# Other_Componentt.net
KiCad netlist of a schematic drawn in Altium Designer
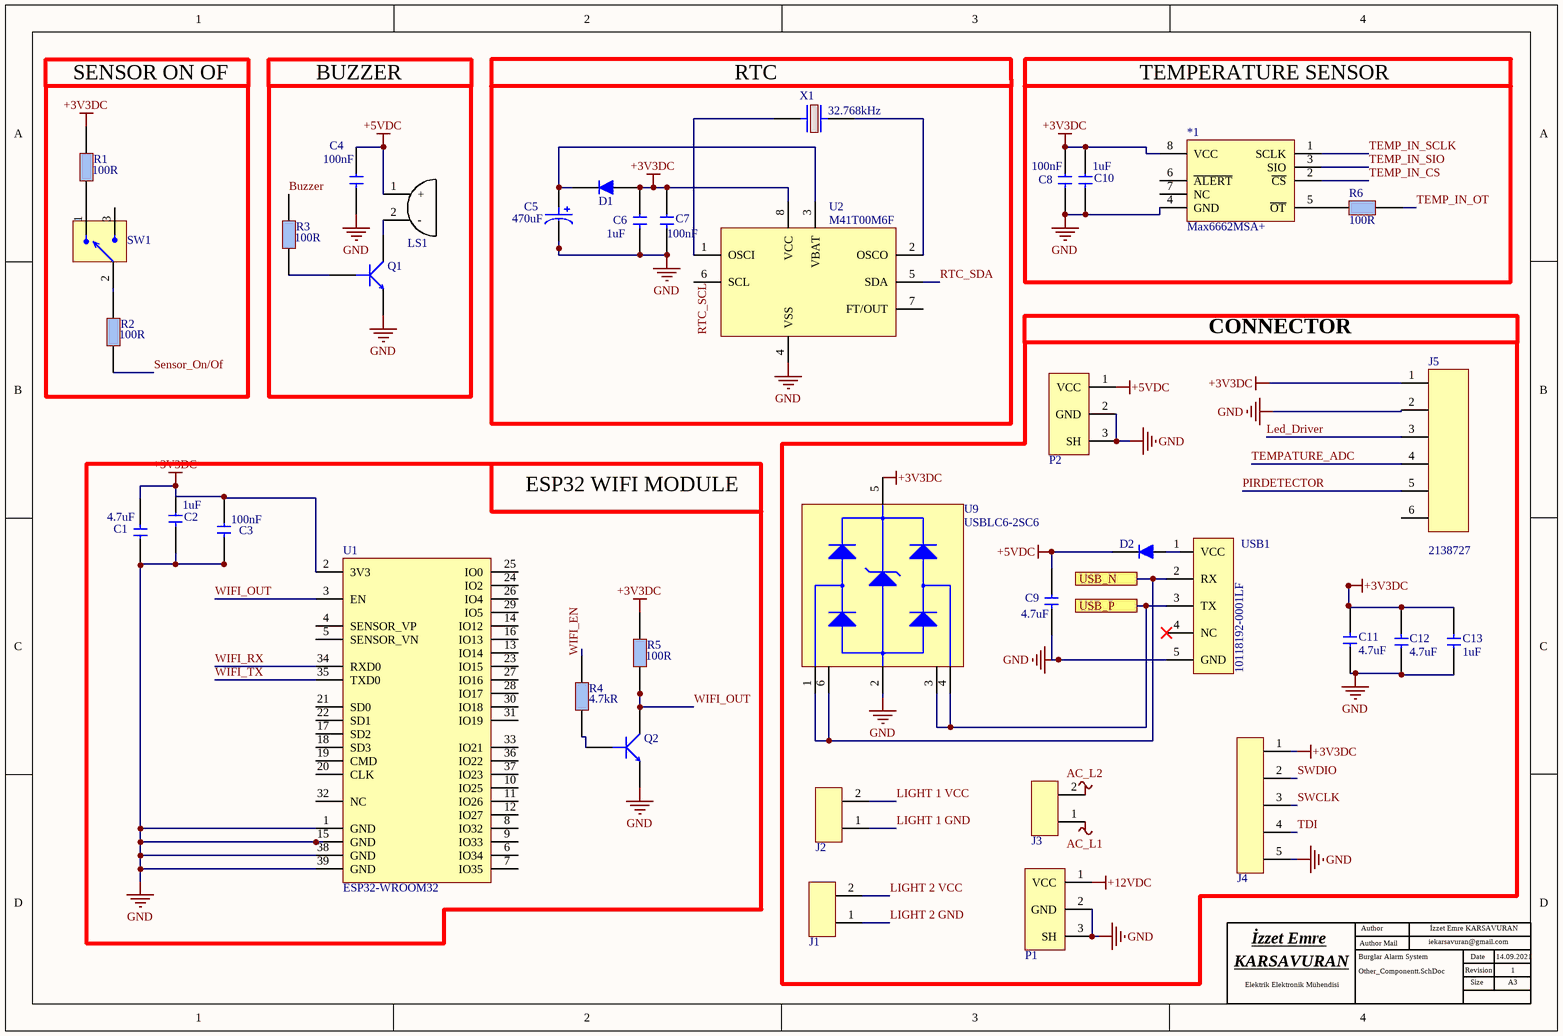
[diagram p0: Other_Componentt.SchDoc]

(export (version "E")
  (design (tool "Eeschema 10.0.6"))
  (components
    (comp (ref "*1")
      (value "Max6662MSA+")
      (footprint "SOIC8")
      (description "Temp Sensor Digital Serial (3-Wire, SPI) 8-Pin SOIC N Tube")
      (fields
        (field (name "MANUFACTURER") "Maxim")
        (field (name "MANUFACTURER PART NUMBER") "MAX6662MSA+")
        (field (name "DESIGNED BY") "İzzet Emre KARSAVURAN")
      )
      (libsource (lib "burglar_alarm_system_Library") (part "Max6662MSA+"))
    )
    (comp (ref "C1")
      (value "CL21A475KAQNNNE")
      (footprint "CAP_0805")
      (fields
        (field (name "MANUFACTURER") "Samsung")
        (field (name "TOLERANCE") "10%")
        (field (name "CAPACITANCE") "4.7uF")
        (field (name "DESIGNED BY") "İzzet Emre KARSAVURAN")
      )
      (libsource (lib "burglar_alarm_system_Library") (part "CAP CER 4.7uF"))
    )
    (comp (ref "C2")
      (value "CL21B105KBFNNNE")
      (footprint "CAP_0805")
      (fields
        (field (name "MANUFACTURER") "Samsung")
        (field (name "TOLERANCE") "10%")
        (field (name "VOLTAGE") "50V")
        (field (name "CAPACITANCE") "1uF")
        (field (name "DESIGNED BY") "İzzet Emre KARSAVURAN")
      )
      (libsource (lib "burglar_alarm_system_Library") (part "CAP CER 1uF"))
    )
    (comp (ref "C3")
      (value "CL21B104KBCNNNC")
      (footprint "CAP_0805")
      (fields
        (field (name "MANUFACTURER") "Samsung")
        (field (name "TOLERANCE") "10%")
        (field (name "VOLTAGE") "50V")
        (field (name "CAPACITANCE") "100nF")
        (field (name "DESIGNED BY") "İzzet Emre KARSAVURAN")
      )
      (libsource (lib "burglar_alarm_system_Library") (part "CAP CER 100nF-0803"))
    )
    (comp (ref "C4")
      (value "CL21B104KBCNNNC")
      (footprint "CAP_0805")
      (fields
        (field (name "MANUFACTURER") "Samsung")
        (field (name "TOLERANCE") "10%")
        (field (name "VOLTAGE") "50V")
        (field (name "CAPACITANCE") "100nF")
        (field (name "DESIGNED BY") "İzzet Emre KARSAVURAN")
      )
      (libsource (lib "burglar_alarm_system_Library") (part "CAP CER 100nF-0803"))
    )
    (comp (ref "C5")
      (value "ESH477M050AH4AA")
      (footprint "CAP_RADIAL_D10_P5")
      (description "Cap, 470UF, 50V, Alu Elec, Radial")
      (fields
        (field (name "MANUFACTURER") "KEMET")
        (field (name "TOLERANCE") "20%")
        (field (name "CAPACITANCE") "470uF")
        (field (name "DESIGNED BY") "İzzet Emre KARSAVURAN")
      )
      (libsource (lib "burglar_alarm_system_Library") (part "CAP ALU ELEC 470uF 50V"))
    )
    (comp (ref "C6")
      (value "CL21B105KBFNNNE")
      (footprint "CAP_0805")
      (fields
        (field (name "MANUFACTURER") "Samsung")
        (field (name "TOLERANCE") "10%")
        (field (name "VOLTAGE") "50V")
        (field (name "CAPACITANCE") "1uF")
        (field (name "DESIGNED BY") "İzzet Emre KARSAVURAN")
      )
      (libsource (lib "burglar_alarm_system_Library") (part "CAP CER 1uF"))
    )
    (comp (ref "C7")
      (value "CL21B104KBCNNNC")
      (footprint "CAP_0805")
      (fields
        (field (name "MANUFACTURER") "Samsung")
        (field (name "TOLERANCE") "10%")
        (field (name "VOLTAGE") "50V")
        (field (name "CAPACITANCE") "100nF")
        (field (name "DESIGNED BY") "İzzet Emre KARSAVURAN")
      )
      (libsource (lib "burglar_alarm_system_Library") (part "CAP CER 100nF-0803"))
    )
    (comp (ref "C8")
      (value "CL21B104KBCNNNC")
      (footprint "CAP_0805")
      (fields
        (field (name "MANUFACTURER") "Samsung")
        (field (name "TOLERANCE") "10%")
        (field (name "VOLTAGE") "50V")
        (field (name "CAPACITANCE") "100nF")
        (field (name "DESIGNED BY") "İzzet Emre KARSAVURAN")
      )
      (libsource (lib "burglar_alarm_system_Library") (part "CAP CER 100nF-0803"))
    )
    (comp (ref "C9")
      (value "CL21A475KAQNNNE")
      (footprint "CAP_0805")
      (fields
        (field (name "MANUFACTURER") "Samsung")
        (field (name "TOLERANCE") "10%")
        (field (name "CAPACITANCE") "4.7uF")
        (field (name "DESIGNED BY") "İzzet Emre KARSAVURAN")
      )
      (libsource (lib "burglar_alarm_system_Library") (part "CAP CER 4.7uF"))
    )
    (comp (ref "C10")
      (value "CL21B105KBFNNNE")
      (footprint "CAP_0805")
      (fields
        (field (name "MANUFACTURER") "Samsung")
        (field (name "TOLERANCE") "10%")
        (field (name "VOLTAGE") "50V")
        (field (name "CAPACITANCE") "1uF")
        (field (name "DESIGNED BY") "İzzet Emre KARSAVURAN")
      )
      (libsource (lib "burglar_alarm_system_Library") (part "CAP CER 1uF"))
    )
    (comp (ref "C11")
      (value "CL21A475KAQNNNE")
      (footprint "CAP_0805")
      (fields
        (field (name "MANUFACTURER") "Samsung")
        (field (name "TOLERANCE") "10%")
        (field (name "CAPACITANCE") "4.7uF")
        (field (name "DESIGNED BY") "İzzet Emre KARSAVURAN")
      )
      (libsource (lib "burglar_alarm_system_Library") (part "CAP CER 4.7uF"))
    )
    (comp (ref "C12")
      (value "CL21A475KAQNNNE")
      (footprint "CAP_0805")
      (fields
        (field (name "MANUFACTURER") "Samsung")
        (field (name "TOLERANCE") "10%")
        (field (name "CAPACITANCE") "4.7uF")
        (field (name "DESIGNED BY") "İzzet Emre KARSAVURAN")
      )
      (libsource (lib "burglar_alarm_system_Library") (part "CAP CER 4.7uF"))
    )
    (comp (ref "C13")
      (value "CL21B105KBFNNNE")
      (footprint "CAP_0805")
      (fields
        (field (name "MANUFACTURER") "Samsung")
        (field (name "TOLERANCE") "10%")
        (field (name "VOLTAGE") "50V")
        (field (name "CAPACITANCE") "1uF")
        (field (name "DESIGNED BY") "İzzet Emre KARSAVURAN")
      )
      (libsource (lib "burglar_alarm_system_Library") (part "CAP CER 1uF"))
    )
    (comp (ref "D1")
      (value "1N4148WS")
      (footprint "SOT23-F")
      (description "ON SEMICONDUCTOR - 1N4148WS - Small Signal Diode, Single, 75 V, 150 mA, 1 V, 4 ns")
      (fields
        (field (name "MANUFACTURER") "ON Semiconductor / Fairchild")
        (field (name "DESIGNED BY") "İzzet Emre KARSAVURAN")
      )
      (libsource (lib "burglar_alarm_system_Library") (part "1N4148WS"))
    )
    (comp (ref "D2")
      (value "1N4148WS")
      (footprint "SOT23-F")
      (description "ON SEMICONDUCTOR - 1N4148WS - Small Signal Diode, Single, 75 V, 150 mA, 1 V, 4 ns")
      (fields
        (field (name "MANUFACTURER") "ON Semiconductor / Fairchild")
        (field (name "DESIGNED BY") "İzzet Emre KARSAVURAN")
      )
      (libsource (lib "burglar_alarm_system_Library") (part "1N4148WS"))
    )
    (comp (ref "J1")
      (value "TBP01R1-508-02BE")
      (footprint "TBP01R1-508")
      (description "Conn Shrouded Header HDR 2 POS 5.08mm Solder RA Side Entry Thru-Hole Bag")
      (fields (field (name "MANUFACTURER") "CUI") (field (name "DESIGNED BY") "İzzet Emre KARSAVURAN"))
      (libsource (lib "burglar_alarm_system_Library") (part "TBP01R1-508-02BE"))
    )
    (comp (ref "J2")
      (value "TBP01R1-508-02BE")
      (footprint "TBP01R1-508")
      (description "Conn Shrouded Header HDR 2 POS 5.08mm Solder RA Side Entry Thru-Hole Bag")
      (fields (field (name "MANUFACTURER") "CUI") (field (name "DESIGNED BY") "İzzet Emre KARSAVURAN"))
      (libsource (lib "burglar_alarm_system_Library") (part "TBP01R1-508-02BE"))
    )
    (comp (ref "J3")
      (value "TBP01R1-508-02BE")
      (footprint "TBP01R1-508")
      (description "Conn Shrouded Header HDR 2 POS 5.08mm Solder RA Side Entry Thru-Hole Bag")
      (fields (field (name "MANUFACTURER") "CUI") (field (name "DESIGNED BY") "İzzet Emre KARSAVURAN"))
      (libsource (lib "burglar_alarm_system_Library") (part "TBP01R1-508-02BE"))
    )
    (comp (ref "J4")
      (value "SMH-105-02-L-S")
      (footprint "PINHEADER1X5_RA")
      (description ".100 C.L. HORIZONTAL SMT SOCKET")
      (fields (field (name "MANUFACTURER") "Samtec") (field (name "DESIGNED BY") "İzzet Emre KARSAVURAN"))
      (libsource (lib "burglar_alarm_system_Library") (part "SMH-105-02-L-S"))
    )
    (comp (ref "J5")
      (value "64800611622")
      (footprint "64800611622")
      (fields
        (field (name "MANUFACTURER") "Wurth Electronics")
        (field (name "SUPPLIER PART NUMBER 1") "2138727")
        (field (name "DESIGNED BY") "İzzet Emre KARSAVURAN")
      )
      (libsource (lib "burglar_alarm_system_Library") (part "64800611622_conn_6pin"))
    )
    (comp (ref "LS1")
      (value "CMI-9605IC-0580T")
      (footprint "CMI-9605IC-0580T")
      (description "Buzzers Indicator, Internally Driven Magnetic 5 V 30mA 2.7kHz 80dB @ 5V, 10cm Through Hole PC Pins")
      (fields (field (name "DESIGNED BY") "İzzet Emre Karsavuran"))
      (libsource (lib "burglar_alarm_system_Library") (part "CMI-9605IC-0580T"))
    )
    (comp (ref "P1")
      (value "PJ-037AH-SMT-TR")
      (footprint "JACK")
      (description "DC Power Connectors Power Jacks")
      (fields (field (name "MANUFACTURER") "CUI") (field (name "DESIGNED BY") "İzzet Emre KARSAVURAN"))
      (libsource (lib "burglar_alarm_system_Library") (part "PJ-037AH-SMT-TR"))
    )
    (comp (ref "P2")
      (value "PJ-037AH-SMT-TR")
      (footprint "JACK")
      (description "DC Power Connectors Power Jacks")
      (fields (field (name "MANUFACTURER") "CUI") (field (name "DESIGNED BY") "İzzet Emre KARSAVURAN"))
      (libsource (lib "burglar_alarm_system_Library") (part "PJ-037AH-SMT-TR"))
    )
    (comp (ref "Q1")
      (value "MMBT3904-7-F")
      (footprint "SOT23-F")
      (description "TRANS NPN 40V 0.2A SMD SOT23-3")
      (fields
        (field (name "MANUFACTURER") "Diodes Zetex")
        (field (name "DESIGNED BY") "İzzet Emre KARSAVURAN")
      )
      (libsource (lib "burglar_alarm_system_Library") (part "MMBT3904-7-F"))
    )
    (comp (ref "Q2")
      (value "MMBT3904-7-F")
      (footprint "SOT23-F")
      (description "TRANS NPN 40V 0.2A SMD SOT23-3")
      (fields
        (field (name "MANUFACTURER") "Diodes Zetex")
        (field (name "DESIGNED BY") "İzzet Emre KARSAVURAN")
      )
      (libsource (lib "burglar_alarm_system_Library") (part "MMBT3904-7-F"))
    )
    (comp (ref "R1")
      (value "RC0603JR-07100RL")
      (footprint "RES_0603")
      (description "Res Thick Film 0603 100 Ohm 5% 0.1W(1/10W) ±100ppm/C Molded SMD Paper T/R")
      (fields
        (field (name "MANUFACTURER") "Yageo")
        (field (name "TOLERANCE") "5%")
        (field (name "RESISTANCE") "100R")
        (field (name "DESIGNED BY") "İzzet Emre KARSAVURAN")
      )
      (libsource (lib "") (part "RES 100 OHM_1"))
    )
    (comp (ref "R2")
      (value "RC0603JR-07100RL")
      (footprint "RES_0603")
      (description "Res Thick Film 0603 100 Ohm 5% 0.1W(1/10W) ±100ppm/C Molded SMD Paper T/R")
      (fields
        (field (name "MANUFACTURER") "Yageo")
        (field (name "TOLERANCE") "5%")
        (field (name "RESISTANCE") "100R")
        (field (name "DESIGNED BY") "İzzet Emre KARSAVURAN")
      )
      (libsource (lib "") (part "RES 100 OHM_1"))
    )
    (comp (ref "R3")
      (value "RC0603JR-07100RL")
      (footprint "RES_0603")
      (description "Res Thick Film 0603 100 Ohm 5% 0.1W(1/10W) ±100ppm/C Molded SMD Paper T/R")
      (fields
        (field (name "MANUFACTURER") "Yageo")
        (field (name "TOLERANCE") "5%")
        (field (name "RESISTANCE") "100R")
        (field (name "DESIGNED BY") "İzzet Emre KARSAVURAN")
      )
      (libsource (lib "") (part "RES 100 OHM_1"))
    )
    (comp (ref "R4")
      (value "RC0603JR-074K7L")
      (footprint "RES_0603")
      (description "Res Thick Film 0603 4.7K Ohm 5% 0.1W(1/10W) ±100ppm/C Molded SMD Paper T/R")
      (fields
        (field (name "MANUFACTURER") "Yageo")
        (field (name "TOLERANCE") "5%")
        (field (name "RESISTANCE") "4.7kR")
        (field (name "DESIGNED BY") "İzzet Emre KARSAVURAN")
      )
      (libsource (lib "burglar_alarm_system_Library") (part "RES 47k OHM"))
    )
    (comp (ref "R5")
      (value "RC0603JR-07100RL")
      (footprint "RES_0603")
      (description "Res Thick Film 0603 100 Ohm 5% 0.1W(1/10W) ±100ppm/C Molded SMD Paper T/R")
      (fields
        (field (name "MANUFACTURER") "Yageo")
        (field (name "TOLERANCE") "5%")
        (field (name "RESISTANCE") "100R")
        (field (name "DESIGNED BY") "İzzet Emre KARSAVURAN")
      )
      (libsource (lib "") (part "RES 100 OHM_1"))
    )
    (comp (ref "R6")
      (value "RC0603JR-07100RL")
      (footprint "RES_0603")
      (description "Res Thick Film 0603 100 Ohm 5% 0.1W(1/10W) ±100ppm/C Molded SMD Paper T/R")
      (fields
        (field (name "MANUFACTURER") "Yageo")
        (field (name "TOLERANCE") "5%")
        (field (name "RESISTANCE") "100R")
        (field (name "DESIGNED BY") "İzzet Emre KARSAVURAN")
      )
      (libsource (lib "burglar_alarm_system_Library") (part "RES 100 OHM"))
    )
    (comp (ref "SW1")
      (value "EG1215AA")
      (footprint "EG1215AA")
      (description "Slide Switch, SPDT, 0.025A, 24V, SMD")
      (fields
        (field (name "MANUFACTURER") "E-Switch")
        (field (name "TOLERANCE") "4.95%")
        (field (name "DESIGNED BY") "İzzet Emre KARSAVURAN")
      )
      (libsource (lib "burglar_alarm_system_Library") (part "EG1215AA"))
    )
    (comp (ref "U1")
      (value "ESP32-WROOM32")
      (footprint "ESP-32")
      (fields
        (field (name "MANUFACTURER") "Espressif Systems")
        (field (name "MANUFACTURER PART NUMBER") "ESP32-WROOM-32E(4MB)")
        (field (name "DESIGNED BY") "İzzet Emre Karsavuran")
      )
      (libsource (lib "burglar_alarm_system_Library") (part "ESP32-WROOM32"))
    )
    (comp (ref "U2")
      (value "M41T00M6F")
      (footprint "SOIC8")
      (description "IC RTC CLK/CALENDAR I2C 8-SOIC")
      (fields
        (field (name "MANUFACTURER") "STMicroelectronics")
        (field (name "DESIGNED BY") "İzzet Emre Karsavuran")
      )
      (libsource (lib "burglar_alarm_system_Library") (part "M41T00M6F"))
    )
    (comp (ref "U9")
      (value "USBLC6-2SC6")
      (footprint "SOT23-6L")
      (description "TVS DIODE 5.25V 17V SOT23-6")
      (fields
        (field (name "MANUFACTURER") "STMicroelectronics")
        (field (name "DESIGNED BY") "İzzet Emre KARSAVURAN")
      )
      (libsource (lib "burglar_alarm_system_Library") (part "USB PROTECTION"))
    )
    (comp (ref "USB1")
      (value "10118192-0001LF")
      (footprint "Micro_Usb_B")
      (description "CONN USB MICRO B RECPT SMT R/A")
      (fields
        (field (name "MANUFACTURER") "Amphenol ICC / FCI")
        (field (name "DESIGNED BY") "İzzet Emre KARSAVURAN")
      )
      (libsource (lib "burglar_alarm_system_Library") (part "Micro B USB Connector"))
    )
    (comp (ref "X1")
      (value "ABS05-32.768KHZ-T")
      (footprint "ABS05")
      (description "ABRACON - ABS05-32.768KHZ-T - Crystal, 32.768 kHz, SMD, 1.6mm x 1mm, 12.5 pF, 20 ppm, ABS05 Series")
      (fields
        (field (name "MANUFACTURER") "Abracon")
        (field (name "TOLERANCE") "20ppm")
        (field (name "FREQUENCY") "32.768kHz")
        (field (name "DESIGNED BY") "İzzet Emre KARSAVURAN")
      )
      (libsource (lib "burglar_alarm_system_Library") (part "CRYSTAL 32768kHZ"))
    )
  )
  (nets
    (net (code "1") (name "+3V3DC") (class "Default")
      (node (ref "*1") (pin "8") (pinfunction "VCC_8") (pintype "passive"))
      (node (ref "C1") (pin "2") (pinfunction "2_2") (pintype "passive"))
      (node (ref "C10") (pin "1") (pinfunction "1_1") (pintype "passive"))
      (node (ref "C11") (pin "2") (pinfunction "2_2") (pintype "passive"))
      (node (ref "C12") (pin "2") (pinfunction "2_2") (pintype "passive"))
      (node (ref "C13") (pin "2") (pinfunction "2_2") (pintype "passive"))
      (node (ref "C2") (pin "1") (pinfunction "1_1") (pintype "passive"))
      (node (ref "C3") (pin "1") (pinfunction "1_1") (pintype "passive"))
      (node (ref "C6") (pin "1") (pinfunction "1_1") (pintype "passive"))
      (node (ref "C7") (pin "1") (pinfunction "1_1") (pintype "passive"))
      (node (ref "C8") (pin "1") (pinfunction "1_1") (pintype "passive"))
      (node (ref "D1") (pin "2") (pinfunction "2_2") (pintype "power_in"))
      (node (ref "J4") (pin "1") (pinfunction "1_1") (pintype "power_in"))
      (node (ref "J5") (pin "1") (pintype "power_in"))
      (node (ref "R1") (pin "2") (pinfunction "2_2") (pintype "passive"))
      (node (ref "R5") (pin "2") (pinfunction "2_2") (pintype "passive"))
      (node (ref "U1") (pin "2") (pinfunction "3V3_2") (pintype "passive"))
      (node (ref "U2") (pin "8") (pinfunction "VCC_8") (pintype "passive"))
      (node (ref "U9") (pin "5") (pinfunction "VBUS_5") (pintype "power_in"))
    )
    (net (code "2") (name "+5VDC") (class "Default")
      (node (ref "C4") (pin "1") (pinfunction "1_1") (pintype "passive"))
      (node (ref "C9") (pin "1") (pinfunction "1_1") (pintype "passive"))
      (node (ref "D2") (pin "1") (pinfunction "1_1") (pintype "power_in"))
      (node (ref "LS1") (pin "1") (pinfunction "+_1") (pintype "passive"))
      (node (ref "P2") (pin "1") (pinfunction "VCC_1") (pintype "power_in"))
    )
    (net (code "3") (name "+12VDC") (class "Default")
      (node (ref "P1") (pin "1") (pinfunction "VCC_1") (pintype "power_in"))
    )
    (net (code "4") (name "/Buzzer") (class "Default")
      (node (ref "R3") (pin "2") (pinfunction "2_2") (pintype "passive"))
    )
    (net (code "5") (name "/LIGHT 1 GND") (class "Default")
      (node (ref "J2") (pin "1") (pinfunction "1_1") (pintype "power_in"))
    )
    (net (code "6") (name "/LIGHT 1 VCC") (class "Default")
      (node (ref "J2") (pin "2") (pinfunction "2_2") (pintype "power_in"))
    )
    (net (code "7") (name "/LIGHT 2 GND") (class "Default")
      (node (ref "J1") (pin "1") (pinfunction "1_1") (pintype "power_in"))
    )
    (net (code "8") (name "/LIGHT 2 VCC") (class "Default")
      (node (ref "J1") (pin "2") (pinfunction "2_2") (pintype "power_in"))
    )
    (net (code "9") (name "/Led_Driver") (class "Default") (node (ref "J5") (pin "3") (pintype "power_in")))
    (net (code "10") (name "/PIRDETECTOR") (class "Default") (node (ref "J5") (pin "5") (pintype "power_in")))
    (net (code "11") (name "/RTC_SCL") (class "Default")
      (node (ref "U2") (pin "6") (pinfunction "SCL_6") (pintype "passive"))
    )
    (net (code "12") (name "/RTC_SDA") (class "Default")
      (node (ref "U2") (pin "5") (pinfunction "SDA_5") (pintype "passive"))
    )
    (net (code "13") (name "/SWCLK") (class "Default")
      (node (ref "J4") (pin "3") (pinfunction "3_3") (pintype "power_in"))
    )
    (net (code "14") (name "/SWDIO") (class "Default")
      (node (ref "J4") (pin "2") (pinfunction "2_2") (pintype "power_in"))
    )
    (net (code "15") (name "/Sensor_On{slash}Of") (class "Default")
      (node (ref "R2") (pin "1") (pinfunction "1_1") (pintype "passive"))
    )
    (net (code "16") (name "/TDI") (class "Default")
      (node (ref "J4") (pin "4") (pinfunction "4_4") (pintype "power_in"))
    )
    (net (code "17") (name "/TEMPATURE_ADC") (class "Default")
      (node (ref "J5") (pin "4") (pintype "power_in"))
    )
    (net (code "18") (name "/TEMP_IN_CS") (class "Default")
      (node (ref "*1") (pin "2") (pinfunction "~{CS}_2") (pintype "passive"))
    )
    (net (code "19") (name "/TEMP_IN_OT") (class "Default")
      (node (ref "R6") (pin "1") (pinfunction "1_1") (pintype "passive"))
    )
    (net (code "20") (name "/TEMP_IN_SCLK") (class "Default")
      (node (ref "*1") (pin "1") (pinfunction "SCLK_1") (pintype "passive"))
    )
    (net (code "21") (name "/TEMP_IN_SIO") (class "Default")
      (node (ref "*1") (pin "3") (pinfunction "SIO_3") (pintype "passive"))
    )
    (net (code "22") (name "/USB_N") (class "Default")
      (node (ref "U9") (pin "1") (pinfunction "I/O1_1") (pintype "power_in"))
      (node (ref "U9") (pin "6") (pinfunction "I/O1_6") (pintype "power_in"))
      (node (ref "USB1") (pin "2") (pinfunction "RX_2") (pintype "power_in"))
    )
    (net (code "23") (name "/USB_P") (class "Default")
      (node (ref "U9") (pin "3") (pinfunction "I/O2_3") (pintype "power_in"))
      (node (ref "U9") (pin "4") (pinfunction "I/O2_4") (pintype "power_in"))
      (node (ref "USB1") (pin "3") (pinfunction "TX_3") (pintype "power_in"))
    )
    (net (code "24") (name "/WIFI_EN") (class "Default")
      (node (ref "R4") (pin "2") (pinfunction "2_2") (pintype "passive"))
    )
    (net (code "25") (name "/WIFI_OUT") (class "Default")
      (node (ref "Q2") (pin "3") (pinfunction "C_3") (pintype "power_in"))
      (node (ref "R5") (pin "1") (pinfunction "1_1") (pintype "passive"))
      (node (ref "U1") (pin "3") (pinfunction "EN_3") (pintype "passive"))
    )
    (net (code "26") (name "/WIFI_RX") (class "Default")
      (node (ref "U1") (pin "34") (pinfunction "RXD0_34") (pintype "passive"))
    )
    (net (code "27") (name "/WIFI_TX") (class "Default")
      (node (ref "U1") (pin "35") (pinfunction "TXD0_35") (pintype "passive"))
    )
    (net (code "28") (name "AC_L1") (class "Default")
      (node (ref "J3") (pin "1") (pinfunction "1_1") (pintype "power_in"))
    )
    (net (code "29") (name "AC_L2") (class "Default")
      (node (ref "J3") (pin "2") (pinfunction "2_2") (pintype "power_in"))
    )
    (net (code "30") (name "GND") (class "Default")
      (node (ref "*1") (pin "4") (pinfunction "GND_4") (pintype "passive"))
      (node (ref "C1") (pin "1") (pinfunction "1_1") (pintype "passive"))
      (node (ref "C10") (pin "2") (pinfunction "2_2") (pintype "passive"))
      (node (ref "C11") (pin "1") (pinfunction "1_1") (pintype "passive"))
      (node (ref "C12") (pin "1") (pinfunction "1_1") (pintype "passive"))
      (node (ref "C13") (pin "1") (pinfunction "1_1") (pintype "passive"))
      (node (ref "C2") (pin "2") (pinfunction "2_2") (pintype "passive"))
      (node (ref "C3") (pin "2") (pinfunction "2_2") (pintype "passive"))
      (node (ref "C4") (pin "2") (pinfunction "2_2") (pintype "passive"))
      (node (ref "C5") (pin "2") (pinfunction "2_2") (pintype "passive"))
      (node (ref "C6") (pin "2") (pinfunction "2_2") (pintype "passive"))
      (node (ref "C7") (pin "2") (pinfunction "2_2") (pintype "passive"))
      (node (ref "C8") (pin "2") (pinfunction "2_2") (pintype "passive"))
      (node (ref "C9") (pin "2") (pinfunction "2_2") (pintype "passive"))
      (node (ref "J4") (pin "5") (pinfunction "5_5") (pintype "power_in"))
      (node (ref "J5") (pin "2") (pintype "power_in"))
      (node (ref "P1") (pin "2") (pinfunction "GND_2") (pintype "power_in"))
      (node (ref "P1") (pin "3") (pinfunction "SH_3") (pintype "power_in"))
      (node (ref "P2") (pin "2") (pinfunction "GND_2") (pintype "power_in"))
      (node (ref "P2") (pin "3") (pinfunction "SH_3") (pintype "power_in"))
      (node (ref "Q1") (pin "2") (pinfunction "E_2") (pintype "power_in"))
      (node (ref "Q2") (pin "2") (pinfunction "E_2") (pintype "power_in"))
      (node (ref "U1") (pin "1") (pinfunction "GND_1") (pintype "passive"))
      (node (ref "U1") (pin "15") (pinfunction "GND_15") (pintype "passive"))
      (node (ref "U1") (pin "38") (pinfunction "GND_38") (pintype "passive"))
      (node (ref "U1") (pin "39") (pinfunction "GND_39") (pintype "passive"))
      (node (ref "U2") (pin "4") (pinfunction "VSS_4") (pintype "passive"))
      (node (ref "U9") (pin "2") (pinfunction "GND_2") (pintype "power_in"))
      (node (ref "USB1") (pin "5") (pinfunction "GND_5") (pintype "power_in"))
    )
    (net (code "31") (name "Net-(*1-~{OT})") (class "Default")
      (node (ref "*1") (pin "5") (pinfunction "~{OT}_5") (pintype "passive"))
      (node (ref "R6") (pin "2") (pinfunction "2_2") (pintype "passive"))
    )
    (net (code "32") (name "Net-(LS1--)") (class "Default")
      (node (ref "LS1") (pin "2") (pinfunction "-_2") (pintype "passive"))
      (node (ref "Q1") (pin "3") (pinfunction "C_3") (pintype "power_in"))
    )
    (net (code "33") (name "Net-(Q1-B)") (class "Default")
      (node (ref "Q1") (pin "1") (pinfunction "B_1") (pintype "power_in"))
      (node (ref "R3") (pin "1") (pinfunction "1_1") (pintype "passive"))
    )
    (net (code "34") (name "Net-(Q2-B)") (class "Default")
      (node (ref "Q2") (pin "1") (pinfunction "B_1") (pintype "power_in"))
      (node (ref "R4") (pin "1") (pinfunction "1_1") (pintype "passive"))
    )
    (net (code "35") (name "Net-(R1-Pad1)") (class "Default")
      (node (ref "R1") (pin "1") (pinfunction "1_1") (pintype "passive"))
      (node (ref "SW1") (pin "1") (pinfunction "1_1") (pintype "passive"))
    )
    (net (code "36") (name "Net-(R2-Pad2)") (class "Default")
      (node (ref "R2") (pin "2") (pinfunction "2_2") (pintype "passive"))
      (node (ref "SW1") (pin "2") (pinfunction "2_2") (pintype "passive"))
    )
    (net (code "37") (name "Net-(U2-OSCI)") (class "Default")
      (node (ref "U2") (pin "1") (pinfunction "OSCI_1") (pintype "passive"))
      (node (ref "X1") (pin "1") (pinfunction "1_1") (pintype "passive"))
    )
    (net (code "38") (name "Net-(U2-OSCO)") (class "Default")
      (node (ref "U2") (pin "2") (pinfunction "OSCO_2") (pintype "passive"))
      (node (ref "X1") (pin "2") (pinfunction "2_2") (pintype "passive"))
    )
    (net (code "39") (name "Net-(U2-VBAT)") (class "Default")
      (node (ref "C5") (pin "1") (pinfunction "1_1") (pintype "passive"))
      (node (ref "D1") (pin "1") (pinfunction "1_1") (pintype "power_in"))
      (node (ref "U2") (pin "3") (pinfunction "VBAT_3") (pintype "passive"))
    )
    (net (code "40") (name "Net-(USB1-VCC)") (class "Default")
      (node (ref "D2") (pin "2") (pinfunction "2_2") (pintype "power_in"))
      (node (ref "USB1") (pin "1") (pinfunction "VCC_1") (pintype "power_in"))
    )
    (net (code "41") (name "unconnected-(*1-NC-Pad7)") (class "Default")
      (node (ref "*1") (pin "7") (pinfunction "NC_7") (pintype "passive"))
    )
    (net (code "42") (name "unconnected-(*1-~{ALERT}-Pad6)") (class "Default")
      (node (ref "*1") (pin "6") (pinfunction "~{ALERT}_6") (pintype "passive"))
    )
    (net (code "43") (name "unconnected-(J5-Pad6)") (class "Default")
      (node (ref "J5") (pin "6") (pintype "power_in"))
    )
    (net (code "44") (name "unconnected-(SW1-Pad3)") (class "Default")
      (node (ref "SW1") (pin "3") (pinfunction "3_3") (pintype "passive"))
    )
    (net (code "45") (name "unconnected-(U1-CLK-Pad20)") (class "Default")
      (node (ref "U1") (pin "20") (pinfunction "CLK_20") (pintype "passive"))
    )
    (net (code "46") (name "unconnected-(U1-CMD-Pad19)") (class "Default")
      (node (ref "U1") (pin "19") (pinfunction "CMD_19") (pintype "passive"))
    )
    (net (code "47") (name "unconnected-(U1-IO0-Pad25)") (class "Default")
      (node (ref "U1") (pin "25") (pinfunction "IO0_25") (pintype "passive"))
    )
    (net (code "48") (name "unconnected-(U1-IO2-Pad24)") (class "Default")
      (node (ref "U1") (pin "24") (pinfunction "IO2_24") (pintype "passive"))
    )
    (net (code "49") (name "unconnected-(U1-IO4-Pad26)") (class "Default")
      (node (ref "U1") (pin "26") (pinfunction "IO4_26") (pintype "passive"))
    )
    (net (code "50") (name "unconnected-(U1-IO5-Pad29)") (class "Default")
      (node (ref "U1") (pin "29") (pinfunction "IO5_29") (pintype "passive"))
    )
    (net (code "51") (name "unconnected-(U1-IO12-Pad14)") (class "Default")
      (node (ref "U1") (pin "14") (pinfunction "IO12_14") (pintype "passive"))
    )
    (net (code "52") (name "unconnected-(U1-IO13-Pad16)") (class "Default")
      (node (ref "U1") (pin "16") (pinfunction "IO13_16") (pintype "passive"))
    )
    (net (code "53") (name "unconnected-(U1-IO14-Pad13)") (class "Default")
      (node (ref "U1") (pin "13") (pinfunction "IO14_13") (pintype "passive"))
    )
    (net (code "54") (name "unconnected-(U1-IO15-Pad23)") (class "Default")
      (node (ref "U1") (pin "23") (pinfunction "IO15_23") (pintype "passive"))
    )
    (net (code "55") (name "unconnected-(U1-IO16-Pad27)") (class "Default")
      (node (ref "U1") (pin "27") (pinfunction "IO16_27") (pintype "passive"))
    )
    (net (code "56") (name "unconnected-(U1-IO17-Pad28)") (class "Default")
      (node (ref "U1") (pin "28") (pinfunction "IO17_28") (pintype "passive"))
    )
    (net (code "57") (name "unconnected-(U1-IO18-Pad30)") (class "Default")
      (node (ref "U1") (pin "30") (pinfunction "IO18_30") (pintype "passive"))
    )
    (net (code "58") (name "unconnected-(U1-IO19-Pad31)") (class "Default")
      (node (ref "U1") (pin "31") (pinfunction "IO19_31") (pintype "passive"))
    )
    (net (code "59") (name "unconnected-(U1-IO21-Pad33)") (class "Default")
      (node (ref "U1") (pin "33") (pinfunction "IO21_33") (pintype "passive"))
    )
    (net (code "60") (name "unconnected-(U1-IO22-Pad36)") (class "Default")
      (node (ref "U1") (pin "36") (pinfunction "IO22_36") (pintype "passive"))
    )
    (net (code "61") (name "unconnected-(U1-IO23-Pad37)") (class "Default")
      (node (ref "U1") (pin "37") (pinfunction "IO23_37") (pintype "passive"))
    )
    (net (code "62") (name "unconnected-(U1-IO25-Pad10)") (class "Default")
      (node (ref "U1") (pin "10") (pinfunction "IO25_10") (pintype "passive"))
    )
    (net (code "63") (name "unconnected-(U1-IO26-Pad11)") (class "Default")
      (node (ref "U1") (pin "11") (pinfunction "IO26_11") (pintype "passive"))
    )
    (net (code "64") (name "unconnected-(U1-IO27-Pad12)") (class "Default")
      (node (ref "U1") (pin "12") (pinfunction "IO27_12") (pintype "passive"))
    )
    (net (code "65") (name "unconnected-(U1-IO32-Pad8)") (class "Default")
      (node (ref "U1") (pin "8") (pinfunction "IO32_8") (pintype "passive"))
    )
    (net (code "66") (name "unconnected-(U1-IO33-Pad9)") (class "Default")
      (node (ref "U1") (pin "9") (pinfunction "IO33_9") (pintype "passive"))
    )
    (net (code "67") (name "unconnected-(U1-IO34-Pad6)") (class "Default")
      (node (ref "U1") (pin "6") (pinfunction "IO34_6") (pintype "passive"))
    )
    (net (code "68") (name "unconnected-(U1-IO35-Pad7)") (class "Default")
      (node (ref "U1") (pin "7") (pinfunction "IO35_7") (pintype "passive"))
    )
    (net (code "69") (name "unconnected-(U1-NC-Pad32)") (class "Default")
      (node (ref "U1") (pin "32") (pinfunction "NC_32") (pintype "passive"))
    )
    (net (code "70") (name "unconnected-(U1-SD0-Pad21)") (class "Default")
      (node (ref "U1") (pin "21") (pinfunction "SD0_21") (pintype "passive"))
    )
    (net (code "71") (name "unconnected-(U1-SD1-Pad22)") (class "Default")
      (node (ref "U1") (pin "22") (pinfunction "SD1_22") (pintype "passive"))
    )
    (net (code "72") (name "unconnected-(U1-SD2-Pad17)") (class "Default")
      (node (ref "U1") (pin "17") (pinfunction "SD2_17") (pintype "passive"))
    )
    (net (code "73") (name "unconnected-(U1-SD3-Pad18)") (class "Default")
      (node (ref "U1") (pin "18") (pinfunction "SD3_18") (pintype "passive"))
    )
    (net (code "74") (name "unconnected-(U1-SENSOR_VN-Pad5)") (class "Default")
      (node (ref "U1") (pin "5") (pinfunction "SENSOR_VN_5") (pintype "passive"))
    )
    (net (code "75") (name "unconnected-(U1-SENSOR_VP-Pad4)") (class "Default")
      (node (ref "U1") (pin "4") (pinfunction "SENSOR_VP_4") (pintype "passive"))
    )
    (net (code "76") (name "unconnected-(U2-FT{slash}OUT-Pad7)") (class "Default")
      (node (ref "U2") (pin "7") (pinfunction "FT/OUT_7") (pintype "passive"))
    )
    (net (code "77") (name "unconnected-(USB1-NC-Pad4)") (class "Default")
      (node (ref "USB1") (pin "4") (pinfunction "NC_4") (pintype "power_in+no_connect"))
    )
  )
)
